# board.net
KiCad netlist of a schematic drawn in EAGLE
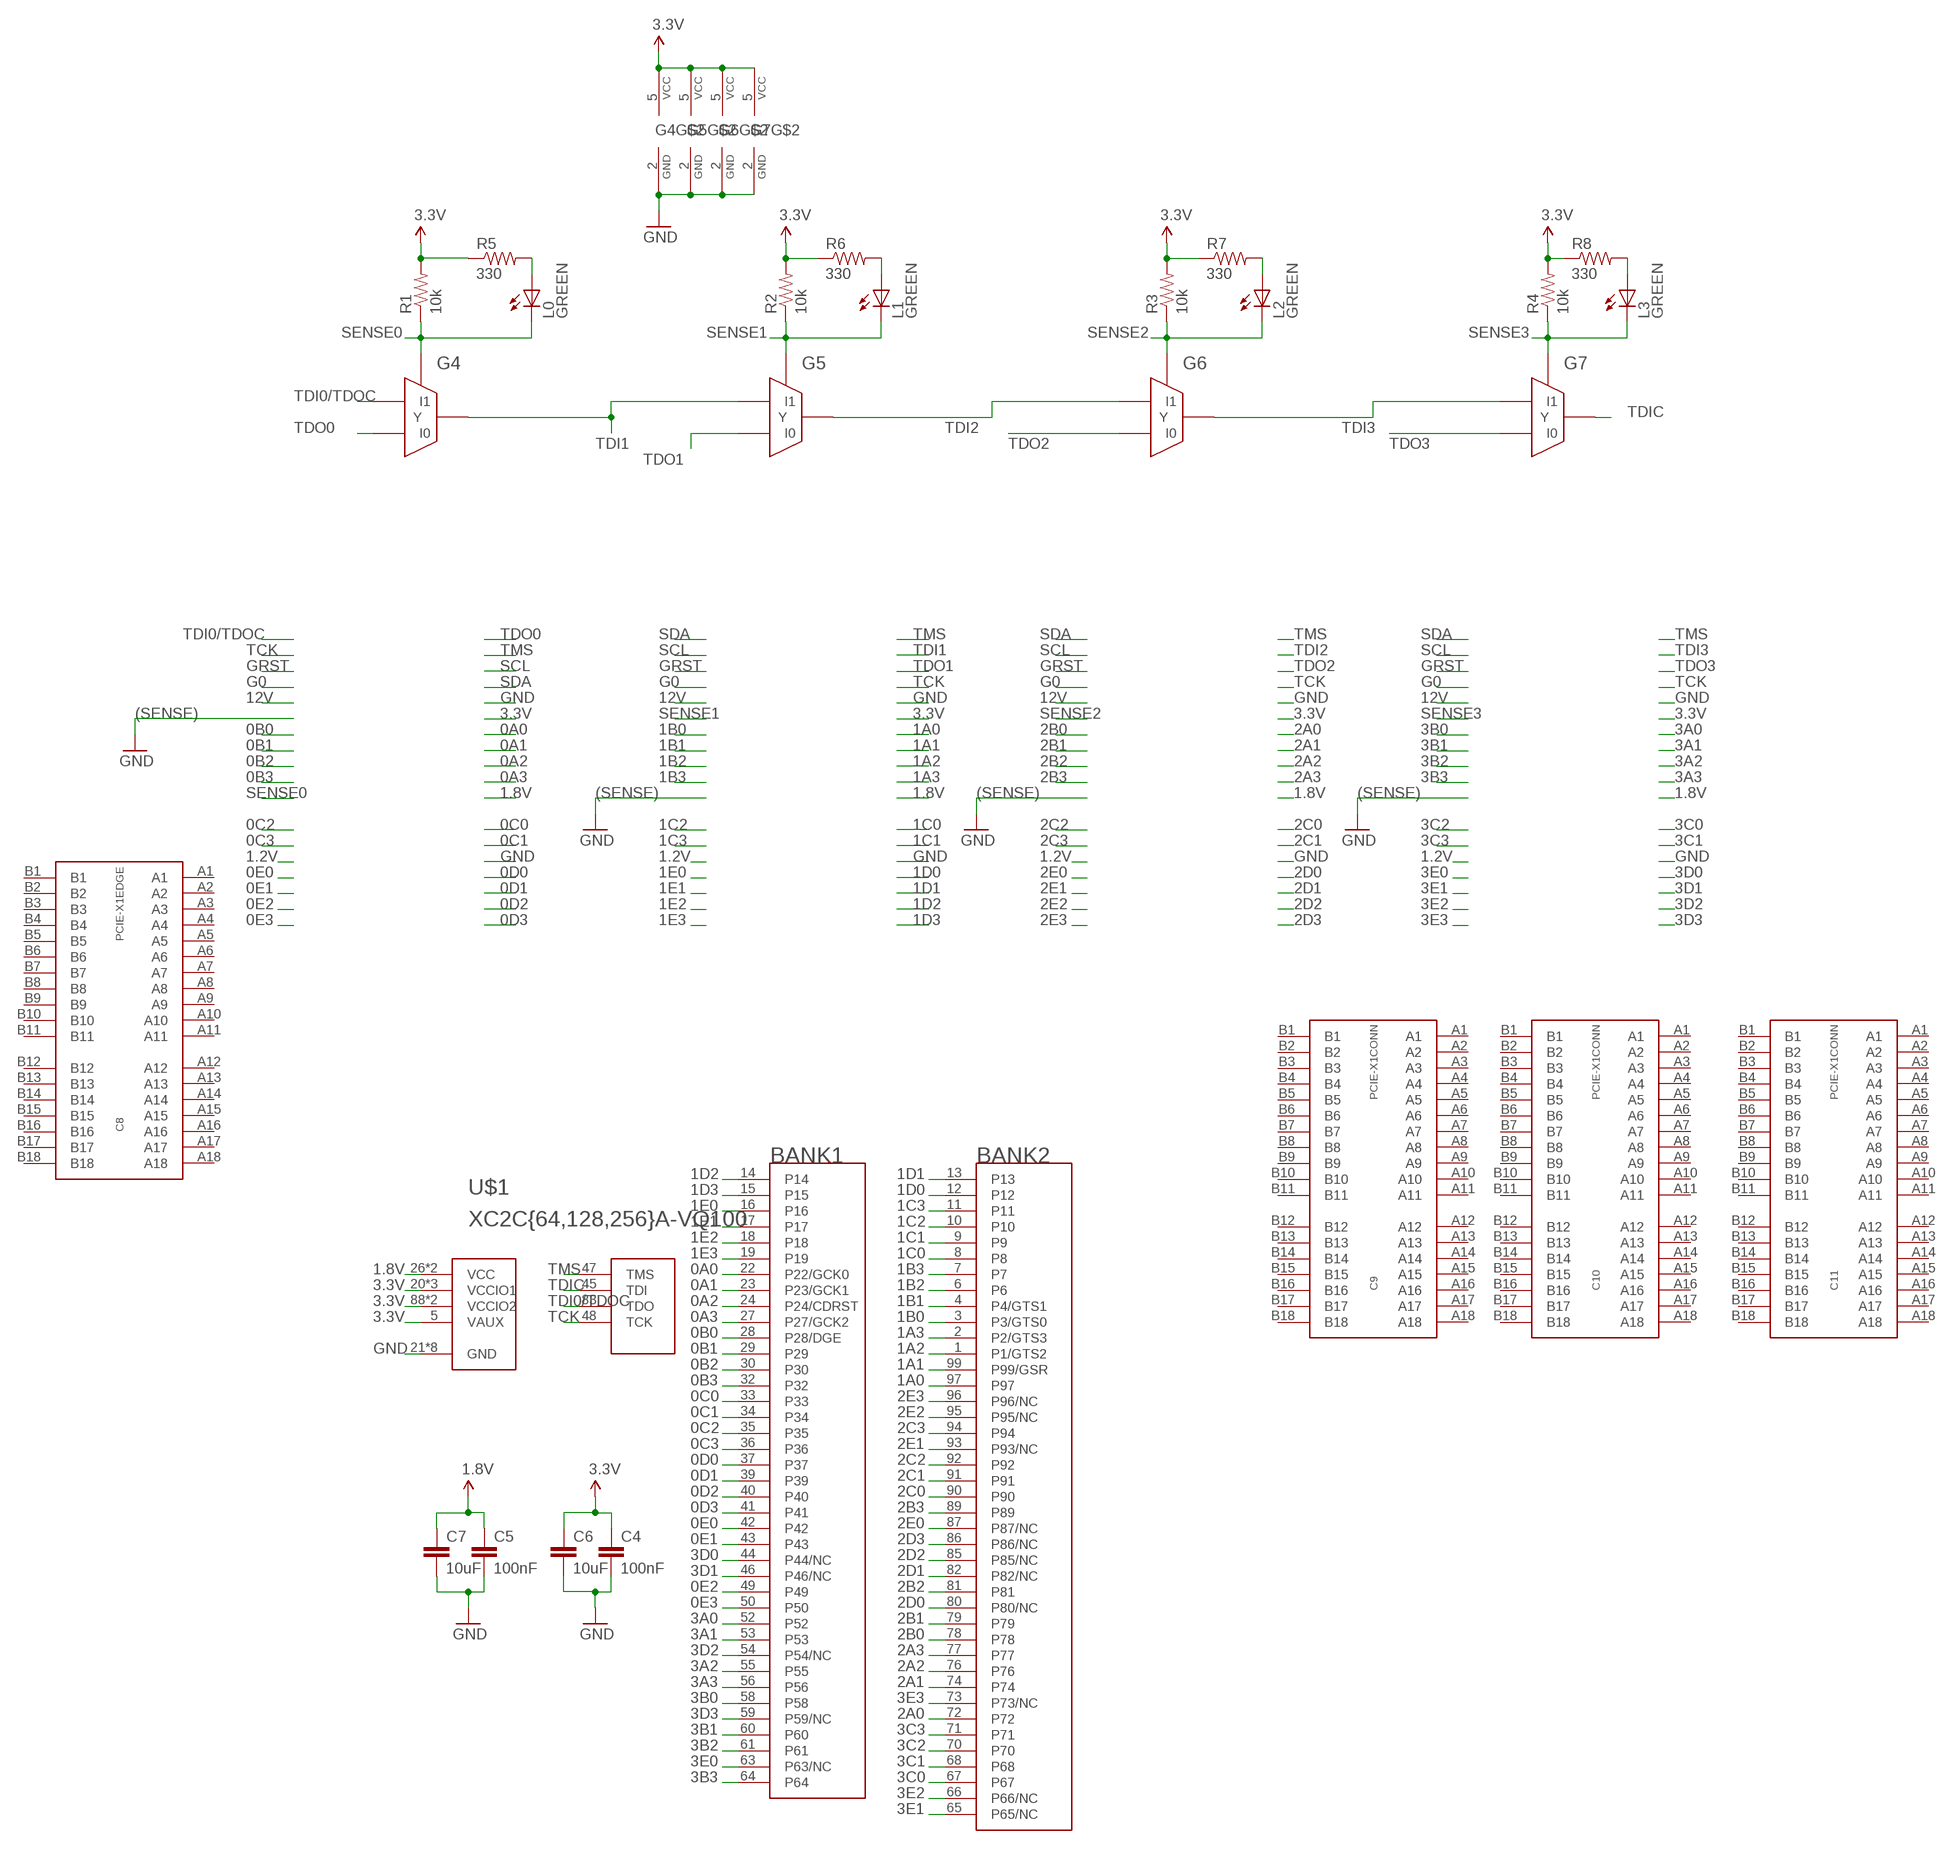
[diagram p0: schematic, sheet 1]

(export (version "E")
  (design (tool "Eeschema 10.0.6"))
  (components
    (comp (ref "C4")
      (value "100nF")
      (footprint "eagle-import:0402-CAP")
      (libsource (lib "eagle-import") (part "CAP0402-CAP"))
    )
    (comp (ref "C5")
      (value "100nF")
      (footprint "eagle-import:0402-CAP")
      (libsource (lib "eagle-import") (part "CAP0402-CAP"))
    )
    (comp (ref "C6")
      (value "10uF")
      (footprint "eagle-import:0805")
      (libsource (lib "eagle-import") (part "CAP0805"))
    )
    (comp (ref "C7")
      (value "10uF")
      (footprint "eagle-import:0805")
      (libsource (lib "eagle-import") (part "CAP0805"))
    )
    (comp (ref "C8")
      (value "PCIE-X1EDGE")
      (footprint "eagle-import:PCIE-X1-EDGE")
      (libsource (lib "eagle-import") (part "PCIE-X1EDGE"))
    )
    (comp (ref "C9")
      (value "PCIE-X1CONN")
      (footprint "eagle-import:PCIE-X1-CONN")
      (libsource (lib "eagle-import") (part "PCIE-X1CONN"))
    )
    (comp (ref "C10")
      (value "PCIE-X1CONN")
      (footprint "eagle-import:PCIE-X1-CONN")
      (libsource (lib "eagle-import") (part "PCIE-X1CONN"))
    )
    (comp (ref "C11")
      (value "PCIE-X1CONN")
      (footprint "eagle-import:PCIE-X1-CONN")
      (libsource (lib "eagle-import") (part "PCIE-X1CONN"))
    )
    (comp (ref "G4")
      (value "74G157")
      (footprint "eagle-import:SOT363")
      (libsource (lib "eagle-import") (part "74G157"))
    )
    (comp (ref "G5")
      (value "74G157")
      (footprint "eagle-import:SOT363")
      (libsource (lib "eagle-import") (part "74G157"))
    )
    (comp (ref "G6")
      (value "74G157")
      (footprint "eagle-import:SOT363")
      (libsource (lib "eagle-import") (part "74G157"))
    )
    (comp (ref "G7")
      (value "74G157")
      (footprint "eagle-import:SOT363")
      (libsource (lib "eagle-import") (part "74G157"))
    )
    (comp (ref "L0")
      (value "GREEN")
      (footprint "eagle-import:0603_LED")
      (libsource (lib "eagle-import") (part "LED0603"))
    )
    (comp (ref "L1")
      (value "GREEN")
      (footprint "eagle-import:0603_LED")
      (libsource (lib "eagle-import") (part "LED0603"))
    )
    (comp (ref "L2")
      (value "GREEN")
      (footprint "eagle-import:0603_LED")
      (libsource (lib "eagle-import") (part "LED0603"))
    )
    (comp (ref "L3")
      (value "GREEN")
      (footprint "eagle-import:0603_LED")
      (libsource (lib "eagle-import") (part "LED0603"))
    )
    (comp (ref "R1")
      (value "10k")
      (footprint "eagle-import:0603-RES")
      (libsource (lib "eagle-import") (part "RESISTOR0603"))
    )
    (comp (ref "R2")
      (value "10k")
      (footprint "eagle-import:0603-RES")
      (libsource (lib "eagle-import") (part "RESISTOR0603"))
    )
    (comp (ref "R3")
      (value "10k")
      (footprint "eagle-import:0603-RES")
      (libsource (lib "eagle-import") (part "RESISTOR0603"))
    )
    (comp (ref "R4")
      (value "10k")
      (footprint "eagle-import:0603-RES")
      (libsource (lib "eagle-import") (part "RESISTOR0603"))
    )
    (comp (ref "R5")
      (value "330")
      (footprint "eagle-import:0603-RES")
      (libsource (lib "eagle-import") (part "RESISTOR0603"))
    )
    (comp (ref "R6")
      (value "330")
      (footprint "eagle-import:0603-RES")
      (libsource (lib "eagle-import") (part "RESISTOR0603"))
    )
    (comp (ref "R7")
      (value "330")
      (footprint "eagle-import:0603-RES")
      (libsource (lib "eagle-import") (part "RESISTOR0603"))
    )
    (comp (ref "R8")
      (value "330")
      (footprint "eagle-import:0603-RES")
      (libsource (lib "eagle-import") (part "RESISTOR0603"))
    )
    (comp (ref "U$1")
      (value "XC2C{64,128,256}A-VQ100")
      (footprint "eagle-import:XILINX_TQ100")
      (libsource (lib "eagle-import") (part "XC2C{64,128,256}A-VQ100"))
    )
  )
  (nets
    (net (code "1") (name "/0A0") (class "Default")
      (node (ref "U$1") (pin "22") (pinfunction "P22/GCK0_22") (pintype "bidirectional"))
    )
    (net (code "2") (name "/0A1") (class "Default")
      (node (ref "U$1") (pin "23") (pinfunction "P23/GCK1_23") (pintype "bidirectional"))
    )
    (net (code "3") (name "/0A2") (class "Default")
      (node (ref "U$1") (pin "24") (pinfunction "P24/CDRST_24") (pintype "bidirectional"))
    )
    (net (code "4") (name "/0A3") (class "Default")
      (node (ref "U$1") (pin "27") (pinfunction "P27/GCK2_27") (pintype "bidirectional"))
    )
    (net (code "5") (name "/0B0") (class "Default")
      (node (ref "U$1") (pin "28") (pinfunction "P28/DGE_28") (pintype "bidirectional"))
    )
    (net (code "6") (name "/0B1") (class "Default")
      (node (ref "U$1") (pin "29") (pinfunction "P29_29") (pintype "bidirectional"))
    )
    (net (code "7") (name "/0B2") (class "Default")
      (node (ref "U$1") (pin "30") (pinfunction "P30_30") (pintype "bidirectional"))
    )
    (net (code "8") (name "/0B3") (class "Default")
      (node (ref "U$1") (pin "32") (pinfunction "P32_32") (pintype "bidirectional"))
    )
    (net (code "9") (name "/0C0") (class "Default")
      (node (ref "U$1") (pin "33") (pinfunction "P33_33") (pintype "bidirectional"))
    )
    (net (code "10") (name "/0C1") (class "Default")
      (node (ref "U$1") (pin "34") (pinfunction "P34_34") (pintype "bidirectional"))
    )
    (net (code "11") (name "/0C2") (class "Default")
      (node (ref "U$1") (pin "35") (pinfunction "P35_35") (pintype "bidirectional"))
    )
    (net (code "12") (name "/0C3") (class "Default")
      (node (ref "U$1") (pin "36") (pinfunction "P36_36") (pintype "bidirectional"))
    )
    (net (code "13") (name "/0D0") (class "Default")
      (node (ref "U$1") (pin "37") (pinfunction "P37_37") (pintype "bidirectional"))
    )
    (net (code "14") (name "/0D1") (class "Default")
      (node (ref "U$1") (pin "39") (pinfunction "P39_39") (pintype "bidirectional"))
    )
    (net (code "15") (name "/0D2") (class "Default")
      (node (ref "U$1") (pin "40") (pinfunction "P40_40") (pintype "bidirectional"))
    )
    (net (code "16") (name "/0D3") (class "Default")
      (node (ref "U$1") (pin "41") (pinfunction "P41_41") (pintype "bidirectional"))
    )
    (net (code "17") (name "/0E0") (class "Default")
      (node (ref "U$1") (pin "42") (pinfunction "P42_42") (pintype "bidirectional"))
    )
    (net (code "18") (name "/0E1") (class "Default")
      (node (ref "U$1") (pin "43") (pinfunction "P43_43") (pintype "bidirectional"))
    )
    (net (code "19") (name "/0E2") (class "Default")
      (node (ref "U$1") (pin "49") (pinfunction "P49_49") (pintype "bidirectional"))
    )
    (net (code "20") (name "/0E3") (class "Default")
      (node (ref "U$1") (pin "50") (pinfunction "P50_50") (pintype "bidirectional"))
    )
    (net (code "22") (name "/1A0") (class "Default")
      (node (ref "U$1") (pin "97") (pinfunction "P97_97") (pintype "bidirectional"))
    )
    (net (code "23") (name "/1A1") (class "Default")
      (node (ref "U$1") (pin "99") (pinfunction "P99/GSR_99") (pintype "bidirectional"))
    )
    (net (code "24") (name "/1A2") (class "Default")
      (node (ref "U$1") (pin "1") (pinfunction "P1/GTS2_1") (pintype "bidirectional"))
    )
    (net (code "25") (name "/1A3") (class "Default")
      (node (ref "U$1") (pin "2") (pinfunction "P2/GTS3_2") (pintype "bidirectional"))
    )
    (net (code "26") (name "/1B0") (class "Default")
      (node (ref "U$1") (pin "3") (pinfunction "P3/GTS0_3") (pintype "bidirectional"))
    )
    (net (code "27") (name "/1B1") (class "Default")
      (node (ref "U$1") (pin "4") (pinfunction "P4/GTS1_4") (pintype "bidirectional"))
    )
    (net (code "28") (name "/1B2") (class "Default")
      (node (ref "U$1") (pin "6") (pinfunction "P6_6") (pintype "bidirectional"))
    )
    (net (code "29") (name "/1B3") (class "Default")
      (node (ref "U$1") (pin "7") (pinfunction "P7_7") (pintype "bidirectional"))
    )
    (net (code "30") (name "/1C0") (class "Default")
      (node (ref "U$1") (pin "8") (pinfunction "P8_8") (pintype "bidirectional"))
    )
    (net (code "31") (name "/1C1") (class "Default")
      (node (ref "U$1") (pin "9") (pinfunction "P9_9") (pintype "bidirectional"))
    )
    (net (code "32") (name "/1C2") (class "Default")
      (node (ref "U$1") (pin "10") (pinfunction "P10_10") (pintype "bidirectional"))
    )
    (net (code "33") (name "/1C3") (class "Default")
      (node (ref "U$1") (pin "11") (pinfunction "P11_11") (pintype "bidirectional"))
    )
    (net (code "34") (name "/1D0") (class "Default")
      (node (ref "U$1") (pin "12") (pinfunction "P12_12") (pintype "bidirectional"))
    )
    (net (code "35") (name "/1D1") (class "Default")
      (node (ref "U$1") (pin "13") (pinfunction "P13_13") (pintype "bidirectional"))
    )
    (net (code "36") (name "/1D2") (class "Default")
      (node (ref "U$1") (pin "14") (pinfunction "P14_14") (pintype "bidirectional"))
    )
    (net (code "37") (name "/1D3") (class "Default")
      (node (ref "U$1") (pin "15") (pinfunction "P15_15") (pintype "bidirectional"))
    )
    (net (code "38") (name "/1E0") (class "Default")
      (node (ref "U$1") (pin "16") (pinfunction "P16_16") (pintype "bidirectional"))
    )
    (net (code "39") (name "/1E1") (class "Default")
      (node (ref "U$1") (pin "17") (pinfunction "P17_17") (pintype "bidirectional"))
    )
    (net (code "40") (name "/1E2") (class "Default")
      (node (ref "U$1") (pin "18") (pinfunction "P18_18") (pintype "bidirectional"))
    )
    (net (code "41") (name "/1E3") (class "Default")
      (node (ref "U$1") (pin "19") (pinfunction "P19_19") (pintype "bidirectional"))
    )
    (net (code "42") (name "/2A0") (class "Default")
      (node (ref "U$1") (pin "72") (pinfunction "P72_72") (pintype "bidirectional"))
    )
    (net (code "43") (name "/2A1") (class "Default")
      (node (ref "U$1") (pin "74") (pinfunction "P74_74") (pintype "bidirectional"))
    )
    (net (code "44") (name "/2A2") (class "Default")
      (node (ref "U$1") (pin "76") (pinfunction "P76_76") (pintype "bidirectional"))
    )
    (net (code "45") (name "/2A3") (class "Default")
      (node (ref "U$1") (pin "77") (pinfunction "P77_77") (pintype "bidirectional"))
    )
    (net (code "46") (name "/2B0") (class "Default")
      (node (ref "U$1") (pin "78") (pinfunction "P78_78") (pintype "bidirectional"))
    )
    (net (code "47") (name "/2B1") (class "Default")
      (node (ref "U$1") (pin "79") (pinfunction "P79_79") (pintype "bidirectional"))
    )
    (net (code "48") (name "/2B2") (class "Default")
      (node (ref "U$1") (pin "81") (pinfunction "P81_81") (pintype "bidirectional"))
    )
    (net (code "49") (name "/2B3") (class "Default")
      (node (ref "U$1") (pin "89") (pinfunction "P89_89") (pintype "bidirectional"))
    )
    (net (code "50") (name "/2C0") (class "Default")
      (node (ref "U$1") (pin "90") (pinfunction "P90_90") (pintype "bidirectional"))
    )
    (net (code "51") (name "/2C1") (class "Default")
      (node (ref "U$1") (pin "91") (pinfunction "P91_91") (pintype "bidirectional"))
    )
    (net (code "52") (name "/2C2") (class "Default")
      (node (ref "U$1") (pin "92") (pinfunction "P92_92") (pintype "bidirectional"))
    )
    (net (code "53") (name "/2C3") (class "Default")
      (node (ref "U$1") (pin "94") (pinfunction "P94_94") (pintype "bidirectional"))
    )
    (net (code "54") (name "/2D0") (class "Default")
      (node (ref "U$1") (pin "80") (pinfunction "P80/NC_80") (pintype "bidirectional"))
    )
    (net (code "55") (name "/2D1") (class "Default")
      (node (ref "U$1") (pin "82") (pinfunction "P82/NC_82") (pintype "bidirectional"))
    )
    (net (code "56") (name "/2D2") (class "Default")
      (node (ref "U$1") (pin "85") (pinfunction "P85/NC_85") (pintype "bidirectional"))
    )
    (net (code "57") (name "/2D3") (class "Default")
      (node (ref "U$1") (pin "86") (pinfunction "P86/NC_86") (pintype "bidirectional"))
    )
    (net (code "58") (name "/2E0") (class "Default")
      (node (ref "U$1") (pin "87") (pinfunction "P87/NC_87") (pintype "bidirectional"))
    )
    (net (code "59") (name "/2E1") (class "Default")
      (node (ref "U$1") (pin "93") (pinfunction "P93/NC_93") (pintype "bidirectional"))
    )
    (net (code "60") (name "/2E2") (class "Default")
      (node (ref "U$1") (pin "95") (pinfunction "P95/NC_95") (pintype "bidirectional"))
    )
    (net (code "61") (name "/2E3") (class "Default")
      (node (ref "U$1") (pin "96") (pinfunction "P96/NC_96") (pintype "bidirectional"))
    )
    (net (code "62") (name "/3A0") (class "Default")
      (node (ref "U$1") (pin "52") (pinfunction "P52_52") (pintype "bidirectional"))
    )
    (net (code "63") (name "/3A1") (class "Default")
      (node (ref "U$1") (pin "53") (pinfunction "P53_53") (pintype "bidirectional"))
    )
    (net (code "64") (name "/3A2") (class "Default")
      (node (ref "U$1") (pin "55") (pinfunction "P55_55") (pintype "bidirectional"))
    )
    (net (code "65") (name "/3A3") (class "Default")
      (node (ref "U$1") (pin "56") (pinfunction "P56_56") (pintype "bidirectional"))
    )
    (net (code "66") (name "/3B0") (class "Default")
      (node (ref "U$1") (pin "58") (pinfunction "P58_58") (pintype "bidirectional"))
    )
    (net (code "67") (name "/3B1") (class "Default")
      (node (ref "U$1") (pin "60") (pinfunction "P60_60") (pintype "bidirectional"))
    )
    (net (code "68") (name "/3B2") (class "Default")
      (node (ref "U$1") (pin "61") (pinfunction "P61_61") (pintype "bidirectional"))
    )
    (net (code "69") (name "/3B3") (class "Default")
      (node (ref "U$1") (pin "64") (pinfunction "P64_64") (pintype "bidirectional"))
    )
    (net (code "70") (name "/3C0") (class "Default")
      (node (ref "U$1") (pin "67") (pinfunction "P67_67") (pintype "bidirectional"))
    )
    (net (code "71") (name "/3C1") (class "Default")
      (node (ref "U$1") (pin "68") (pinfunction "P68_68") (pintype "bidirectional"))
    )
    (net (code "72") (name "/3C2") (class "Default")
      (node (ref "U$1") (pin "70") (pinfunction "P70_70") (pintype "bidirectional"))
    )
    (net (code "73") (name "/3C3") (class "Default")
      (node (ref "U$1") (pin "71") (pinfunction "P71_71") (pintype "bidirectional"))
    )
    (net (code "74") (name "/3D0") (class "Default")
      (node (ref "U$1") (pin "44") (pinfunction "P44/NC_44") (pintype "bidirectional"))
    )
    (net (code "75") (name "/3D1") (class "Default")
      (node (ref "U$1") (pin "46") (pinfunction "P46/NC_46") (pintype "bidirectional"))
    )
    (net (code "76") (name "/3D2") (class "Default")
      (node (ref "U$1") (pin "54") (pinfunction "P54/NC_54") (pintype "bidirectional"))
    )
    (net (code "77") (name "/3D3") (class "Default")
      (node (ref "U$1") (pin "59") (pinfunction "P59/NC_59") (pintype "bidirectional"))
    )
    (net (code "78") (name "/3E0") (class "Default")
      (node (ref "U$1") (pin "63") (pinfunction "P63/NC_63") (pintype "bidirectional"))
    )
    (net (code "79") (name "/3E1") (class "Default")
      (node (ref "U$1") (pin "65") (pinfunction "P65/NC_65") (pintype "bidirectional"))
    )
    (net (code "80") (name "/3E2") (class "Default")
      (node (ref "U$1") (pin "66") (pinfunction "P66/NC_66") (pintype "bidirectional"))
    )
    (net (code "81") (name "/3E3") (class "Default")
      (node (ref "U$1") (pin "73") (pinfunction "P73/NC_73") (pintype "bidirectional"))
    )
    (net (code "87") (name "/SENSE0") (class "Default")
      (node (ref "G4") (pin "6") (pinfunction "S_6") (pintype "input"))
      (node (ref "L0") (pin "C") (pinfunction "C_C") (pintype "passive"))
      (node (ref "R1") (pin "1") (pinfunction "1_1") (pintype "passive"))
    )
    (net (code "88") (name "/SENSE1") (class "Default")
      (node (ref "G5") (pin "6") (pinfunction "S_6") (pintype "input"))
      (node (ref "L1") (pin "C") (pinfunction "C_C") (pintype "passive"))
      (node (ref "R2") (pin "1") (pinfunction "1_1") (pintype "passive"))
    )
    (net (code "89") (name "/SENSE2") (class "Default")
      (node (ref "G6") (pin "6") (pinfunction "S_6") (pintype "input"))
      (node (ref "L2") (pin "C") (pinfunction "C_C") (pintype "passive"))
      (node (ref "R3") (pin "1") (pinfunction "1_1") (pintype "passive"))
    )
    (net (code "90") (name "/SENSE3") (class "Default")
      (node (ref "G7") (pin "6") (pinfunction "S_6") (pintype "input"))
      (node (ref "L3") (pin "C") (pinfunction "C_C") (pintype "passive"))
      (node (ref "R4") (pin "1") (pinfunction "1_1") (pintype "passive"))
    )
    (net (code "91") (name "/TCK") (class "Default")
      (node (ref "U$1") (pin "48") (pinfunction "TCK_48") (pintype "bidirectional"))
    )
    (net (code "92") (name "/TDI0{slash}TDOC") (class "Default")
      (node (ref "G4") (pin "1") (pinfunction "I1_1") (pintype "input"))
      (node (ref "U$1") (pin "83") (pinfunction "TDO_83") (pintype "bidirectional"))
    )
    (net (code "93") (name "/TDI1") (class "Default")
      (node (ref "G4") (pin "4") (pinfunction "Y_4") (pintype "output"))
      (node (ref "G5") (pin "1") (pinfunction "I1_1") (pintype "input"))
    )
    (net (code "94") (name "/TDI2") (class "Default")
      (node (ref "G5") (pin "4") (pinfunction "Y_4") (pintype "output"))
      (node (ref "G6") (pin "1") (pinfunction "I1_1") (pintype "input"))
    )
    (net (code "95") (name "/TDI3") (class "Default")
      (node (ref "G6") (pin "4") (pinfunction "Y_4") (pintype "output"))
      (node (ref "G7") (pin "1") (pinfunction "I1_1") (pintype "input"))
    )
    (net (code "96") (name "/TDIC") (class "Default")
      (node (ref "G7") (pin "4") (pinfunction "Y_4") (pintype "output"))
      (node (ref "U$1") (pin "45") (pinfunction "TDI_45") (pintype "bidirectional"))
    )
    (net (code "97") (name "/TDO0") (class "Default")
      (node (ref "G4") (pin "3") (pinfunction "I0_3") (pintype "input"))
    )
    (net (code "98") (name "/TDO1") (class "Default")
      (node (ref "G5") (pin "3") (pinfunction "I0_3") (pintype "input"))
    )
    (net (code "99") (name "/TDO2") (class "Default")
      (node (ref "G6") (pin "3") (pinfunction "I0_3") (pintype "input"))
    )
    (net (code "100") (name "/TDO3") (class "Default")
      (node (ref "G7") (pin "3") (pinfunction "I0_3") (pintype "input"))
    )
    (net (code "101") (name "/TMS") (class "Default")
      (node (ref "U$1") (pin "47") (pinfunction "TMS_47") (pintype "bidirectional"))
    )
    (net (code "102") (name "1.8V") (class "Default")
      (node (ref "C5") (pin "1") (pinfunction "1_1") (pintype "passive"))
      (node (ref "C7") (pin "1") (pinfunction "1_1") (pintype "passive"))
      (node (ref "U$1") (pin "26") (pinfunction "VCC_26") (pintype "bidirectional"))
      (node (ref "U$1") (pin "57") (pinfunction "VCC_57") (pintype "bidirectional"))
    )
    (net (code "103") (name "3.3V") (class "Default")
      (node (ref "C4") (pin "1") (pinfunction "1_1") (pintype "passive"))
      (node (ref "C6") (pin "1") (pinfunction "1_1") (pintype "passive"))
      (node (ref "G4") (pin "5") (pinfunction "VCC_5") (pintype "power_in"))
      (node (ref "G5") (pin "5") (pinfunction "VCC_5") (pintype "power_in"))
      (node (ref "G6") (pin "5") (pinfunction "VCC_5") (pintype "power_in"))
      (node (ref "G7") (pin "5") (pinfunction "VCC_5") (pintype "power_in"))
      (node (ref "R1") (pin "2") (pinfunction "2_2") (pintype "passive"))
      (node (ref "R2") (pin "2") (pinfunction "2_2") (pintype "passive"))
      (node (ref "R3") (pin "2") (pinfunction "2_2") (pintype "passive"))
      (node (ref "R4") (pin "2") (pinfunction "2_2") (pintype "passive"))
      (node (ref "R5") (pin "1") (pinfunction "1_1") (pintype "passive"))
      (node (ref "R6") (pin "1") (pinfunction "1_1") (pintype "passive"))
      (node (ref "R7") (pin "1") (pinfunction "1_1") (pintype "passive"))
      (node (ref "R8") (pin "1") (pinfunction "1_1") (pintype "passive"))
      (node (ref "U$1") (pin "20") (pinfunction "VCCIO1_20") (pintype "bidirectional"))
      (node (ref "U$1") (pin "38") (pinfunction "VCCIO1_38") (pintype "bidirectional"))
      (node (ref "U$1") (pin "5") (pinfunction "VAUX_5") (pintype "bidirectional"))
      (node (ref "U$1") (pin "51") (pinfunction "VCCIO1_51") (pintype "bidirectional"))
      (node (ref "U$1") (pin "88") (pinfunction "VCCIO2_88") (pintype "bidirectional"))
      (node (ref "U$1") (pin "98") (pinfunction "VCCIO2_98") (pintype "bidirectional"))
    )
    (net (code "104") (name "GND") (class "Default")
      (node (ref "C4") (pin "2") (pinfunction "2_2") (pintype "passive"))
      (node (ref "C5") (pin "2") (pinfunction "2_2") (pintype "passive"))
      (node (ref "C6") (pin "2") (pinfunction "2_2") (pintype "passive"))
      (node (ref "C7") (pin "2") (pinfunction "2_2") (pintype "passive"))
      (node (ref "G4") (pin "2") (pinfunction "GND_2") (pintype "power_in"))
      (node (ref "G5") (pin "2") (pinfunction "GND_2") (pintype "power_in"))
      (node (ref "G6") (pin "2") (pinfunction "GND_2") (pintype "power_in"))
      (node (ref "G7") (pin "2") (pinfunction "GND_2") (pintype "power_in"))
      (node (ref "U$1") (pin "100") (pinfunction "GND_100") (pintype "bidirectional"))
      (node (ref "U$1") (pin "21") (pinfunction "GND_21") (pintype "bidirectional"))
      (node (ref "U$1") (pin "25") (pinfunction "GND_25") (pintype "bidirectional"))
      (node (ref "U$1") (pin "31") (pinfunction "GND_31") (pintype "bidirectional"))
      (node (ref "U$1") (pin "62") (pinfunction "GND_62") (pintype "bidirectional"))
      (node (ref "U$1") (pin "69") (pinfunction "GND_69") (pintype "bidirectional"))
      (node (ref "U$1") (pin "75") (pinfunction "GND_75") (pintype "bidirectional"))
      (node (ref "U$1") (pin "84") (pinfunction "GND_84") (pintype "bidirectional"))
    )
    (net (code "105") (name "Net-(L0-PadA)") (class "Default")
      (node (ref "L0") (pin "A") (pinfunction "A_A") (pintype "passive"))
      (node (ref "R5") (pin "2") (pinfunction "2_2") (pintype "passive"))
    )
    (net (code "106") (name "Net-(L1-PadA)") (class "Default")
      (node (ref "L1") (pin "A") (pinfunction "A_A") (pintype "passive"))
      (node (ref "R6") (pin "2") (pinfunction "2_2") (pintype "passive"))
    )
    (net (code "107") (name "Net-(L2-PadA)") (class "Default")
      (node (ref "L2") (pin "A") (pinfunction "A_A") (pintype "passive"))
      (node (ref "R7") (pin "2") (pinfunction "2_2") (pintype "passive"))
    )
    (net (code "108") (name "Net-(L3-PadA)") (class "Default")
      (node (ref "L3") (pin "A") (pinfunction "A_A") (pintype "passive"))
      (node (ref "R8") (pin "2") (pinfunction "2_2") (pintype "passive"))
    )
    (net (code "109") (name "unconnected-(C8-PadA1)") (class "Default")
      (node (ref "C8") (pin "A1") (pinfunction "A1_A1") (pintype "bidirectional"))
    )
    (net (code "110") (name "unconnected-(C8-PadA2)") (class "Default")
      (node (ref "C8") (pin "A2") (pinfunction "A2_A2") (pintype "bidirectional"))
    )
    (net (code "111") (name "unconnected-(C8-PadA3)") (class "Default")
      (node (ref "C8") (pin "A3") (pinfunction "A3_A3") (pintype "bidirectional"))
    )
    (net (code "112") (name "unconnected-(C8-PadA4)") (class "Default")
      (node (ref "C8") (pin "A4") (pinfunction "A4_A4") (pintype "bidirectional"))
    )
    (net (code "113") (name "unconnected-(C8-PadA5)") (class "Default")
      (node (ref "C8") (pin "A5") (pinfunction "A5_A5") (pintype "bidirectional"))
    )
    (net (code "114") (name "unconnected-(C8-PadA6)") (class "Default")
      (node (ref "C8") (pin "A6") (pinfunction "A6_A6") (pintype "bidirectional"))
    )
    (net (code "115") (name "unconnected-(C8-PadA7)") (class "Default")
      (node (ref "C8") (pin "A7") (pinfunction "A7_A7") (pintype "bidirectional"))
    )
    (net (code "116") (name "unconnected-(C8-PadA8)") (class "Default")
      (node (ref "C8") (pin "A8") (pinfunction "A8_A8") (pintype "bidirectional"))
    )
    (net (code "117") (name "unconnected-(C8-PadA9)") (class "Default")
      (node (ref "C8") (pin "A9") (pinfunction "A9_A9") (pintype "bidirectional"))
    )
    (net (code "118") (name "unconnected-(C8-PadA10)") (class "Default")
      (node (ref "C8") (pin "A10") (pinfunction "A10_A10") (pintype "bidirectional"))
    )
    (net (code "119") (name "unconnected-(C8-PadA11)") (class "Default")
      (node (ref "C8") (pin "A11") (pinfunction "A11_A11") (pintype "bidirectional"))
    )
    (net (code "120") (name "unconnected-(C8-PadA12)") (class "Default")
      (node (ref "C8") (pin "A12") (pinfunction "A12_A12") (pintype "bidirectional"))
    )
    (net (code "121") (name "unconnected-(C8-PadA13)") (class "Default")
      (node (ref "C8") (pin "A13") (pinfunction "A13_A13") (pintype "bidirectional"))
    )
    (net (code "122") (name "unconnected-(C8-PadA14)") (class "Default")
      (node (ref "C8") (pin "A14") (pinfunction "A14_A14") (pintype "bidirectional"))
    )
    (net (code "123") (name "unconnected-(C8-PadA15)") (class "Default")
      (node (ref "C8") (pin "A15") (pinfunction "A15_A15") (pintype "bidirectional"))
    )
    (net (code "124") (name "unconnected-(C8-PadA16)") (class "Default")
      (node (ref "C8") (pin "A16") (pinfunction "A16_A16") (pintype "bidirectional"))
    )
    (net (code "125") (name "unconnected-(C8-PadA17)") (class "Default")
      (node (ref "C8") (pin "A17") (pinfunction "A17_A17") (pintype "bidirectional"))
    )
    (net (code "126") (name "unconnected-(C8-PadA18)") (class "Default")
      (node (ref "C8") (pin "A18") (pinfunction "A18_A18") (pintype "bidirectional"))
    )
    (net (code "127") (name "unconnected-(C8-PadB1)") (class "Default")
      (node (ref "C8") (pin "B1") (pinfunction "B1_B1") (pintype "bidirectional"))
    )
    (net (code "128") (name "unconnected-(C8-PadB2)") (class "Default")
      (node (ref "C8") (pin "B2") (pinfunction "B2_B2") (pintype "bidirectional"))
    )
    (net (code "129") (name "unconnected-(C8-PadB3)") (class "Default")
      (node (ref "C8") (pin "B3") (pinfunction "B3_B3") (pintype "bidirectional"))
    )
    (net (code "130") (name "unconnected-(C8-PadB4)") (class "Default")
      (node (ref "C8") (pin "B4") (pinfunction "B4_B4") (pintype "bidirectional"))
    )
    (net (code "131") (name "unconnected-(C8-PadB5)") (class "Default")
      (node (ref "C8") (pin "B5") (pinfunction "B5_B5") (pintype "bidirectional"))
    )
    (net (code "132") (name "unconnected-(C8-PadB6)") (class "Default")
      (node (ref "C8") (pin "B6") (pinfunction "B6_B6") (pintype "bidirectional"))
    )
    (net (code "133") (name "unconnected-(C8-PadB7)") (class "Default")
      (node (ref "C8") (pin "B7") (pinfunction "B7_B7") (pintype "bidirectional"))
    )
    (net (code "134") (name "unconnected-(C8-PadB8)") (class "Default")
      (node (ref "C8") (pin "B8") (pinfunction "B8_B8") (pintype "bidirectional"))
    )
    (net (code "135") (name "unconnected-(C8-PadB9)") (class "Default")
      (node (ref "C8") (pin "B9") (pinfunction "B9_B9") (pintype "bidirectional"))
    )
    (net (code "136") (name "unconnected-(C8-PadB10)") (class "Default")
      (node (ref "C8") (pin "B10") (pinfunction "B10_B10") (pintype "bidirectional"))
    )
    (net (code "137") (name "unconnected-(C8-PadB11)") (class "Default")
      (node (ref "C8") (pin "B11") (pinfunction "B11_B11") (pintype "bidirectional"))
    )
    (net (code "138") (name "unconnected-(C8-PadB12)") (class "Default")
      (node (ref "C8") (pin "B12") (pinfunction "B12_B12") (pintype "bidirectional"))
    )
    (net (code "139") (name "unconnected-(C8-PadB13)") (class "Default")
      (node (ref "C8") (pin "B13") (pinfunction "B13_B13") (pintype "bidirectional"))
    )
    (net (code "140") (name "unconnected-(C8-PadB14)") (class "Default")
      (node (ref "C8") (pin "B14") (pinfunction "B14_B14") (pintype "bidirectional"))
    )
    (net (code "141") (name "unconnected-(C8-PadB15)") (class "Default")
      (node (ref "C8") (pin "B15") (pinfunction "B15_B15") (pintype "bidirectional"))
    )
    (net (code "142") (name "unconnected-(C8-PadB16)") (class "Default")
      (node (ref "C8") (pin "B16") (pinfunction "B16_B16") (pintype "bidirectional"))
    )
    (net (code "143") (name "unconnected-(C8-PadB17)") (class "Default")
      (node (ref "C8") (pin "B17") (pinfunction "B17_B17") (pintype "bidirectional"))
    )
    (net (code "144") (name "unconnected-(C8-PadB18)") (class "Default")
      (node (ref "C8") (pin "B18") (pinfunction "B18_B18") (pintype "bidirectional"))
    )
    (net (code "145") (name "unconnected-(C9-PadA1)") (class "Default")
      (node (ref "C9") (pin "A1") (pinfunction "A1_A1") (pintype "bidirectional"))
    )
    (net (code "146") (name "unconnected-(C9-PadA2)") (class "Default")
      (node (ref "C9") (pin "A2") (pinfunction "A2_A2") (pintype "bidirectional"))
    )
    (net (code "147") (name "unconnected-(C9-PadA3)") (class "Default")
      (node (ref "C9") (pin "A3") (pinfunction "A3_A3") (pintype "bidirectional"))
    )
    (net (code "148") (name "unconnected-(C9-PadA4)") (class "Default")
      (node (ref "C9") (pin "A4") (pinfunction "A4_A4") (pintype "bidirectional"))
    )
    (net (code "149") (name "unconnected-(C9-PadA5)") (class "Default")
      (node (ref "C9") (pin "A5") (pinfunction "A5_A5") (pintype "bidirectional"))
    )
    (net (code "150") (name "unconnected-(C9-PadA6)") (class "Default")
      (node (ref "C9") (pin "A6") (pinfunction "A6_A6") (pintype "bidirectional"))
    )
    (net (code "151") (name "unconnected-(C9-PadA7)") (class "Default")
      (node (ref "C9") (pin "A7") (pinfunction "A7_A7") (pintype "bidirectional"))
    )
    (net (code "152") (name "unconnected-(C9-PadA8)") (class "Default")
      (node (ref "C9") (pin "A8") (pinfunction "A8_A8") (pintype "bidirectional"))
    )
    (net (code "153") (name "unconnected-(C9-PadA9)") (class "Default")
      (node (ref "C9") (pin "A9") (pinfunction "A9_A9") (pintype "bidirectional"))
    )
    (net (code "154") (name "unconnected-(C9-PadA10)") (class "Default")
      (node (ref "C9") (pin "A10") (pinfunction "A10_A10") (pintype "bidirectional"))
    )
    (net (code "155") (name "unconnected-(C9-PadA11)") (class "Default")
      (node (ref "C9") (pin "A11") (pinfunction "A11_A11") (pintype "bidirectional"))
    )
    (net (code "156") (name "unconnected-(C9-PadA12)") (class "Default")
      (node (ref "C9") (pin "A12") (pinfunction "A12_A12") (pintype "bidirectional"))
    )
    (net (code "157") (name "unconnected-(C9-PadA13)") (class "Default")
      (node (ref "C9") (pin "A13") (pinfunction "A13_A13") (pintype "bidirectional"))
    )
    (net (code "158") (name "unconnected-(C9-PadA14)") (class "Default")
      (node (ref "C9") (pin "A14") (pinfunction "A14_A14") (pintype "bidirectional"))
    )
    (net (code "159") (name "unconnected-(C9-PadA15)") (class "Default")
      (node (ref "C9") (pin "A15") (pinfunction "A15_A15") (pintype "bidirectional"))
    )
    (net (code "160") (name "unconnected-(C9-PadA16)") (class "Default")
      (node (ref "C9") (pin "A16") (pinfunction "A16_A16") (pintype "bidirectional"))
    )
    (net (code "161") (name "unconnected-(C9-PadA17)") (class "Default")
      (node (ref "C9") (pin "A17") (pinfunction "A17_A17") (pintype "bidirectional"))
    )
    (net (code "162") (name "unconnected-(C9-PadA18)") (class "Default")
      (node (ref "C9") (pin "A18") (pinfunction "A18_A18") (pintype "bidirectional"))
    )
    (net (code "163") (name "unconnected-(C9-PadB1)") (class "Default")
      (node (ref "C9") (pin "B1") (pinfunction "B1_B1") (pintype "bidirectional"))
    )
    (net (code "164") (name "unconnected-(C9-PadB2)") (class "Default")
      (node (ref "C9") (pin "B2") (pinfunction "B2_B2") (pintype "bidirectional"))
    )
    (net (code "165") (name "unconnected-(C9-PadB3)") (class "Default")
      (node (ref "C9") (pin "B3") (pinfunction "B3_B3") (pintype "bidirectional"))
    )
    (net (code "166") (name "unconnected-(C9-PadB4)") (class "Default")
      (node (ref "C9") (pin "B4") (pinfunction "B4_B4") (pintype "bidirectional"))
    )
    (net (code "167") (name "unconnected-(C9-PadB5)") (class "Default")
      (node (ref "C9") (pin "B5") (pinfunction "B5_B5") (pintype "bidirectional"))
    )
    (net (code "168") (name "unconnected-(C9-PadB6)") (class "Default")
      (node (ref "C9") (pin "B6") (pinfunction "B6_B6") (pintype "bidirectional"))
    )
    (net (code "169") (name "unconnected-(C9-PadB7)") (class "Default")
      (node (ref "C9") (pin "B7") (pinfunction "B7_B7") (pintype "bidirectional"))
    )
    (net (code "170") (name "unconnected-(C9-PadB8)") (class "Default")
      (node (ref "C9") (pin "B8") (pinfunction "B8_B8") (pintype "bidirectional"))
    )
    (net (code "171") (name "unconnected-(C9-PadB9)") (class "Default")
      (node (ref "C9") (pin "B9") (pinfunction "B9_B9") (pintype "bidirectional"))
    )
    (net (code "172") (name "unconnected-(C9-PadB10)") (class "Default")
      (node (ref "C9") (pin "B10") (pinfunction "B10_B10") (pintype "bidirectional"))
    )
    (net (code "173") (name "unconnected-(C9-PadB11)") (class "Default")
      (node (ref "C9") (pin "B11") (pinfunction "B11_B11") (pintype "bidirectional"))
    )
    (net (code "174") (name "unconnected-(C9-PadB12)") (class "Default")
      (node (ref "C9") (pin "B12") (pinfunction "B12_B12") (pintype "bidirectional"))
    )
    (net (code "175") (name "unconnected-(C9-PadB13)") (class "Default")
      (node (ref "C9") (pin "B13") (pinfunction "B13_B13") (pintype "bidirectional"))
    )
    (net (code "176") (name "unconnected-(C9-PadB14)") (class "Default")
      (node (ref "C9") (pin "B14") (pinfunction "B14_B14") (pintype "bidirectional"))
    )
    (net (code "177") (name "unconnected-(C9-PadB15)") (class "Default")
      (node (ref "C9") (pin "B15") (pinfunction "B15_B15") (pintype "bidirectional"))
    )
    (net (code "178") (name "unconnected-(C9-PadB16)") (class "Default")
      (node (ref "C9") (pin "B16") (pinfunction "B16_B16") (pintype "bidirectional"))
    )
    (net (code "179") (name "unconnected-(C9-PadB17)") (class "Default")
      (node (ref "C9") (pin "B17") (pinfunction "B17_B17") (pintype "bidirectional"))
    )
    (net (code "180") (name "unconnected-(C9-PadB18)") (class "Default")
      (node (ref "C9") (pin "B18") (pinfunction "B18_B18") (pintype "bidirectional"))
    )
    (net (code "181") (name "unconnected-(C10-PadA1)") (class "Default")
      (node (ref "C10") (pin "A1") (pinfunction "A1_A1") (pintype "bidirectional"))
    )
    (net (code "182") (name "unconnected-(C10-PadA2)") (class "Default")
      (node (ref "C10") (pin "A2") (pinfunction "A2_A2") (pintype "bidirectional"))
    )
    (net (code "183") (name "unconnected-(C10-PadA3)") (class "Default")
      (node (ref "C10") (pin "A3") (pinfunction "A3_A3") (pintype "bidirectional"))
    )
    (net (code "184") (name "unconnected-(C10-PadA4)") (class "Default")
      (node (ref "C10") (pin "A4") (pinfunction "A4_A4") (pintype "bidirectional"))
    )
    (net (code "185") (name "unconnected-(C10-PadA5)") (class "Default")
      (node (ref "C10") (pin "A5") (pinfunction "A5_A5") (pintype "bidirectional"))
    )
    (net (code "186") (name "unconnected-(C10-PadA6)") (class "Default")
      (node (ref "C10") (pin "A6") (pinfunction "A6_A6") (pintype "bidirectional"))
    )
    (net (code "187") (name "unconnected-(C10-PadA7)") (class "Default")
      (node (ref "C10") (pin "A7") (pinfunction "A7_A7") (pintype "bidirectional"))
    )
    (net (code "188") (name "unconnected-(C10-PadA8)") (class "Default")
      (node (ref "C10") (pin "A8") (pinfunction "A8_A8") (pintype "bidirectional"))
    )
    (net (code "189") (name "unconnected-(C10-PadA9)") (class "Default")
      (node (ref "C10") (pin "A9") (pinfunction "A9_A9") (pintype "bidirectional"))
    )
    (net (code "190") (name "unconnected-(C10-PadA10)") (class "Default")
      (node (ref "C10") (pin "A10") (pinfunction "A10_A10") (pintype "bidirectional"))
    )
    (net (code "191") (name "unconnected-(C10-PadA11)") (class "Default")
      (node (ref "C10") (pin "A11") (pinfunction "A11_A11") (pintype "bidirectional"))
    )
    (net (code "192") (name "unconnected-(C10-PadA12)") (class "Default")
      (node (ref "C10") (pin "A12") (pinfunction "A12_A12") (pintype "bidirectional"))
    )
    (net (code "193") (name "unconnected-(C10-PadA13)") (class "Default")
      (node (ref "C10") (pin "A13") (pinfunction "A13_A13") (pintype "bidirectional"))
    )
    (net (code "194") (name "unconnected-(C10-PadA14)") (class "Default")
      (node (ref "C10") (pin "A14") (pinfunction "A14_A14") (pintype "bidirectional"))
    )
    (net (code "195") (name "unconnected-(C10-PadA15)") (class "Default")
      (node (ref "C10") (pin "A15") (pinfunction "A15_A15") (pintype "bidirectional"))
    )
    (net (code "196") (name "unconnected-(C10-PadA16)") (class "Default")
      (node (ref "C10") (pin "A16") (pinfunction "A16_A16") (pintype "bidirectional"))
    )
    (net (code "197") (name "unconnected-(C10-PadA17)") (class "Default")
      (node (ref "C10") (pin "A17") (pinfunction "A17_A17") (pintype "bidirectional"))
    )
    (net (code "198") (name "unconnected-(C10-PadA18)") (class "Default")
      (node (ref "C10") (pin "A18") (pinfunction "A18_A18") (pintype "bidirectional"))
    )
    (net (code "199") (name "unconnected-(C10-PadB1)") (class "Default")
      (node (ref "C10") (pin "B1") (pinfunction "B1_B1") (pintype "bidirectional"))
    )
    (net (code "200") (name "unconnected-(C10-PadB2)") (class "Default")
      (node (ref "C10") (pin "B2") (pinfunction "B2_B2") (pintype "bidirectional"))
    )
    (net (code "201") (name "unconnected-(C10-PadB3)") (class "Default")
      (node (ref "C10") (pin "B3") (pinfunction "B3_B3") (pintype "bidirectional"))
    )
    (net (code "202") (name "unconnected-(C10-PadB4)") (class "Default")
      (node (ref "C10") (pin "B4") (pinfunction "B4_B4") (pintype "bidirectional"))
    )
    (net (code "203") (name "unconnected-(C10-PadB5)") (class "Default")
      (node (ref "C10") (pin "B5") (pinfunction "B5_B5") (pintype "bidirectional"))
    )
    (net (code "204") (name "unconnected-(C10-PadB6)") (class "Default")
      (node (ref "C10") (pin "B6") (pinfunction "B6_B6") (pintype "bidirectional"))
    )
    (net (code "205") (name "unconnected-(C10-PadB7)") (class "Default")
      (node (ref "C10") (pin "B7") (pinfunction "B7_B7") (pintype "bidirectional"))
    )
    (net (code "206") (name "unconnected-(C10-PadB8)") (class "Default")
      (node (ref "C10") (pin "B8") (pinfunction "B8_B8") (pintype "bidirectional"))
    )
    (net (code "207") (name "unconnected-(C10-PadB9)") (class "Default")
      (node (ref "C10") (pin "B9") (pinfunction "B9_B9") (pintype "bidirectional"))
    )
    (net (code "208") (name "unconnected-(C10-PadB10)") (class "Default")
      (node (ref "C10") (pin "B10") (pinfunction "B10_B10") (pintype "bidirectional"))
    )
    (net (code "209") (name "unconnected-(C10-PadB11)") (class "Default")
      (node (ref "C10") (pin "B11") (pinfunction "B11_B11") (pintype "bidirectional"))
    )
    (net (code "210") (name "unconnected-(C10-PadB12)") (class "Default")
      (node (ref "C10") (pin "B12") (pinfunction "B12_B12") (pintype "bidirectional"))
    )
    (net (code "211") (name "unconnected-(C10-PadB13)") (class "Default")
      (node (ref "C10") (pin "B13") (pinfunction "B13_B13") (pintype "bidirectional"))
    )
    (net (code "212") (name "unconnected-(C10-PadB14)") (class "Default")
      (node (ref "C10") (pin "B14") (pinfunction "B14_B14") (pintype "bidirectional"))
    )
    (net (code "213") (name "unconnected-(C10-PadB15)") (class "Default")
      (node (ref "C10") (pin "B15") (pinfunction "B15_B15") (pintype "bidirectional"))
    )
    (net (code "214") (name "unconnected-(C10-PadB16)") (class "Default")
      (node (ref "C10") (pin "B16") (pinfunction "B16_B16") (pintype "bidirectional"))
    )
    (net (code "215") (name "unconnected-(C10-PadB17)") (class "Default")
      (node (ref "C10") (pin "B17") (pinfunction "B17_B17") (pintype "bidirectional"))
    )
    (net (code "216") (name "unconnected-(C10-PadB18)") (class "Default")
      (node (ref "C10") (pin "B18") (pinfunction "B18_B18") (pintype "bidirectional"))
    )
    (net (code "217") (name "unconnected-(C11-PadA1)") (class "Default")
      (node (ref "C11") (pin "A1") (pinfunction "A1_A1") (pintype "bidirectional"))
    )
    (net (code "218") (name "unconnected-(C11-PadA2)") (class "Default")
      (node (ref "C11") (pin "A2") (pinfunction "A2_A2") (pintype "bidirectional"))
    )
    (net (code "219") (name "unconnected-(C11-PadA3)") (class "Default")
      (node (ref "C11") (pin "A3") (pinfunction "A3_A3") (pintype "bidirectional"))
    )
    (net (code "220") (name "unconnected-(C11-PadA4)") (class "Default")
      (node (ref "C11") (pin "A4") (pinfunction "A4_A4") (pintype "bidirectional"))
    )
    (net (code "221") (name "unconnected-(C11-PadA5)") (class "Default")
      (node (ref "C11") (pin "A5") (pinfunction "A5_A5") (pintype "bidirectional"))
    )
    (net (code "222") (name "unconnected-(C11-PadA6)") (class "Default")
      (node (ref "C11") (pin "A6") (pinfunction "A6_A6") (pintype "bidirectional"))
    )
    (net (code "223") (name "unconnected-(C11-PadA7)") (class "Default")
      (node (ref "C11") (pin "A7") (pinfunction "A7_A7") (pintype "bidirectional"))
    )
    (net (code "224") (name "unconnected-(C11-PadA8)") (class "Default")
      (node (ref "C11") (pin "A8") (pinfunction "A8_A8") (pintype "bidirectional"))
    )
    (net (code "225") (name "unconnected-(C11-PadA9)") (class "Default")
      (node (ref "C11") (pin "A9") (pinfunction "A9_A9") (pintype "bidirectional"))
    )
    (net (code "226") (name "unconnected-(C11-PadA10)") (class "Default")
      (node (ref "C11") (pin "A10") (pinfunction "A10_A10") (pintype "bidirectional"))
    )
    (net (code "227") (name "unconnected-(C11-PadA11)") (class "Default")
      (node (ref "C11") (pin "A11") (pinfunction "A11_A11") (pintype "bidirectional"))
    )
    (net (code "228") (name "unconnected-(C11-PadA12)") (class "Default")
      (node (ref "C11") (pin "A12") (pinfunction "A12_A12") (pintype "bidirectional"))
    )
    (net (code "229") (name "unconnected-(C11-PadA13)") (class "Default")
      (node (ref "C11") (pin "A13") (pinfunction "A13_A13") (pintype "bidirectional"))
    )
    (net (code "230") (name "unconnected-(C11-PadA14)") (class "Default")
      (node (ref "C11") (pin "A14") (pinfunction "A14_A14") (pintype "bidirectional"))
    )
    (net (code "231") (name "unconnected-(C11-PadA15)") (class "Default")
      (node (ref "C11") (pin "A15") (pinfunction "A15_A15") (pintype "bidirectional"))
    )
    (net (code "232") (name "unconnected-(C11-PadA16)") (class "Default")
      (node (ref "C11") (pin "A16") (pinfunction "A16_A16") (pintype "bidirectional"))
    )
    (net (code "233") (name "unconnected-(C11-PadA17)") (class "Default")
      (node (ref "C11") (pin "A17") (pinfunction "A17_A17") (pintype "bidirectional"))
    )
    (net (code "234") (name "unconnected-(C11-PadA18)") (class "Default")
      (node (ref "C11") (pin "A18") (pinfunction "A18_A18") (pintype "bidirectional"))
    )
    (net (code "235") (name "unconnected-(C11-PadB1)") (class "Default")
      (node (ref "C11") (pin "B1") (pinfunction "B1_B1") (pintype "bidirectional"))
    )
    (net (code "236") (name "unconnected-(C11-PadB2)") (class "Default")
      (node (ref "C11") (pin "B2") (pinfunction "B2_B2") (pintype "bidirectional"))
    )
    (net (code "237") (name "unconnected-(C11-PadB3)") (class "Default")
      (node (ref "C11") (pin "B3") (pinfunction "B3_B3") (pintype "bidirectional"))
    )
    (net (code "238") (name "unconnected-(C11-PadB4)") (class "Default")
      (node (ref "C11") (pin "B4") (pinfunction "B4_B4") (pintype "bidirectional"))
    )
    (net (code "239") (name "unconnected-(C11-PadB5)") (class "Default")
      (node (ref "C11") (pin "B5") (pinfunction "B5_B5") (pintype "bidirectional"))
    )
    (net (code "240") (name "unconnected-(C11-PadB6)") (class "Default")
      (node (ref "C11") (pin "B6") (pinfunction "B6_B6") (pintype "bidirectional"))
    )
    (net (code "241") (name "unconnected-(C11-PadB7)") (class "Default")
      (node (ref "C11") (pin "B7") (pinfunction "B7_B7") (pintype "bidirectional"))
    )
    (net (code "242") (name "unconnected-(C11-PadB8)") (class "Default")
      (node (ref "C11") (pin "B8") (pinfunction "B8_B8") (pintype "bidirectional"))
    )
    (net (code "243") (name "unconnected-(C11-PadB9)") (class "Default")
      (node (ref "C11") (pin "B9") (pinfunction "B9_B9") (pintype "bidirectional"))
    )
    (net (code "244") (name "unconnected-(C11-PadB10)") (class "Default")
      (node (ref "C11") (pin "B10") (pinfunction "B10_B10") (pintype "bidirectional"))
    )
    (net (code "245") (name "unconnected-(C11-PadB11)") (class "Default")
      (node (ref "C11") (pin "B11") (pinfunction "B11_B11") (pintype "bidirectional"))
    )
    (net (code "246") (name "unconnected-(C11-PadB12)") (class "Default")
      (node (ref "C11") (pin "B12") (pinfunction "B12_B12") (pintype "bidirectional"))
    )
    (net (code "247") (name "unconnected-(C11-PadB13)") (class "Default")
      (node (ref "C11") (pin "B13") (pinfunction "B13_B13") (pintype "bidirectional"))
    )
    (net (code "248") (name "unconnected-(C11-PadB14)") (class "Default")
      (node (ref "C11") (pin "B14") (pinfunction "B14_B14") (pintype "bidirectional"))
    )
    (net (code "249") (name "unconnected-(C11-PadB15)") (class "Default")
      (node (ref "C11") (pin "B15") (pinfunction "B15_B15") (pintype "bidirectional"))
    )
    (net (code "250") (name "unconnected-(C11-PadB16)") (class "Default")
      (node (ref "C11") (pin "B16") (pinfunction "B16_B16") (pintype "bidirectional"))
    )
    (net (code "251") (name "unconnected-(C11-PadB17)") (class "Default")
      (node (ref "C11") (pin "B17") (pinfunction "B17_B17") (pintype "bidirectional"))
    )
    (net (code "252") (name "unconnected-(C11-PadB18)") (class "Default")
      (node (ref "C11") (pin "B18") (pinfunction "B18_B18") (pintype "bidirectional"))
    )
  )
)
